# AD590.net
KiCad netlist of a schematic drawn in EAGLE
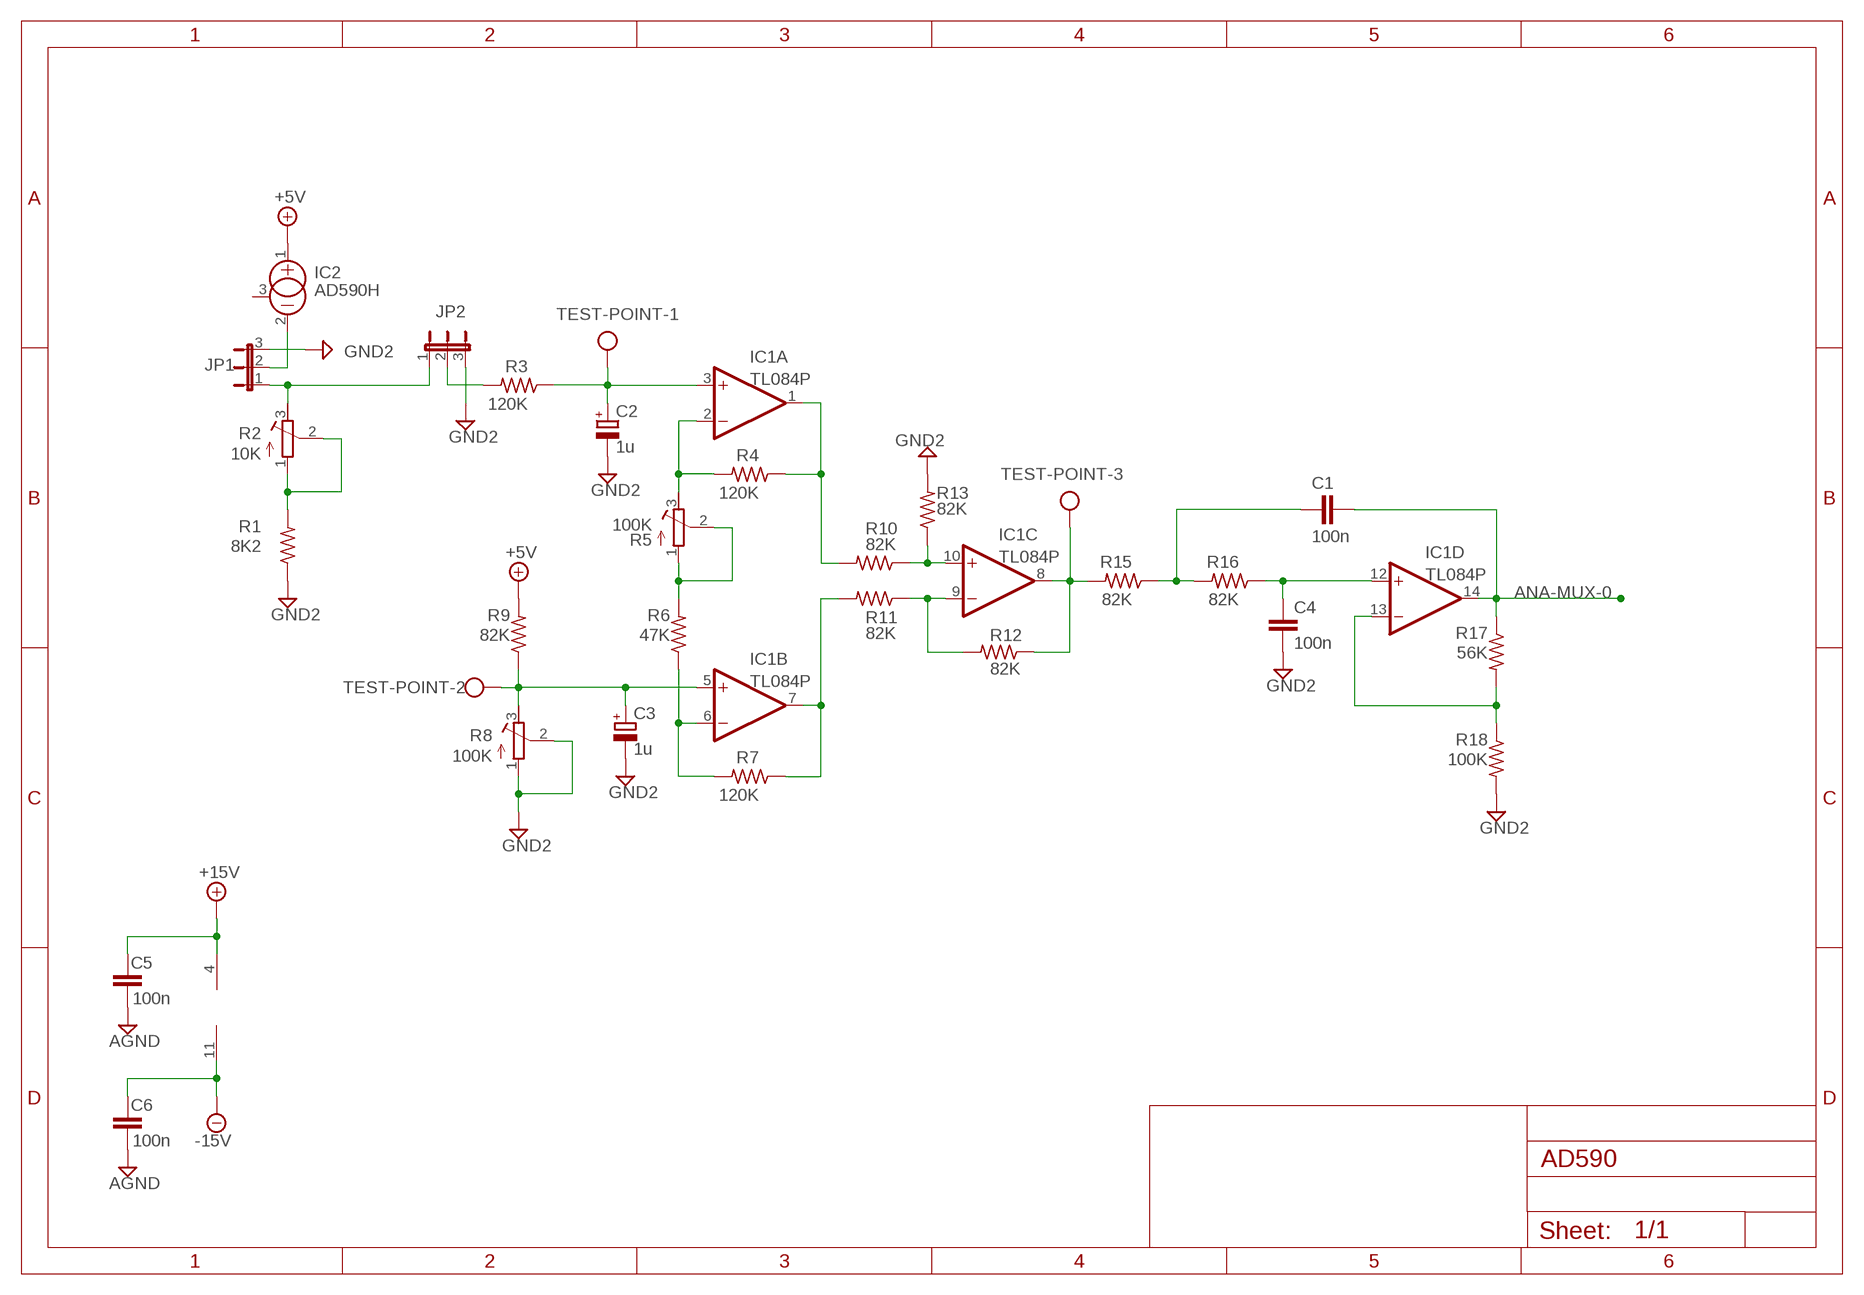
[diagram p0: schematic, sheet 1]

(export (version "E")
  (design (tool "Eeschema 10.0.6"))
  (components
    (comp (ref "C1")
      (value "100n")
      (footprint "eagle-import:C025-024X044")
      (libsource (lib "eagle-import") (part "C-EU025-024X044"))
    )
    (comp (ref "C2")
      (value "1u")
      (footprint "eagle-import:B45181C")
      (libsource (lib "eagle-import") (part "CPOL-EUB45181C"))
    )
    (comp (ref "C3")
      (value "1u")
      (footprint "eagle-import:B45181C")
      (libsource (lib "eagle-import") (part "CPOL-EUB45181C"))
    )
    (comp (ref "C4")
      (value "100n")
      (footprint "eagle-import:C025-024X044")
      (libsource (lib "eagle-import") (part "C-EU025-024X044"))
    )
    (comp (ref "C5")
      (value "100n")
      (footprint "eagle-import:C025-024X044")
      (libsource (lib "eagle-import") (part "C-EU025-024X044"))
    )
    (comp (ref "C6")
      (value "100n")
      (footprint "eagle-import:C025-024X044")
      (libsource (lib "eagle-import") (part "C-EU025-024X044"))
    )
    (comp (ref "IC1")
      (value "TL084P")
      (footprint "eagle-import:DIL14")
      (libsource (lib "eagle-import") (part "TL084P"))
    )
    (comp (ref "IC2")
      (value "AD590H")
      (footprint "eagle-import:TO18")
      (libsource (lib "eagle-import") (part "AD590H"))
    )
    (comp (ref "JP1")
      (value "JP2E")
      (footprint "eagle-import:JP2")
      (libsource (lib "eagle-import") (part "JP2E"))
    )
    (comp (ref "JP2")
      (value "JP2E")
      (footprint "eagle-import:JP2")
      (libsource (lib "eagle-import") (part "JP2E"))
    )
    (comp (ref "R1")
      (value "8K2")
      (footprint "eagle-import:0204_7")
      (libsource (lib "eagle-import") (part "R-US_0204/7"))
    )
    (comp (ref "R2")
      (value "10K")
      (footprint "eagle-import:RTRIM64W")
      (libsource (lib "eagle-import") (part "R-TRIMM64W"))
    )
    (comp (ref "R3")
      (value "120K")
      (footprint "eagle-import:0204_7")
      (libsource (lib "eagle-import") (part "R-US_0204/7"))
    )
    (comp (ref "R4")
      (value "120K")
      (footprint "eagle-import:0204_7")
      (libsource (lib "eagle-import") (part "R-US_0204/7"))
    )
    (comp (ref "R5")
      (value "100K")
      (footprint "eagle-import:RTRIM64W")
      (libsource (lib "eagle-import") (part "R-TRIMM64W"))
    )
    (comp (ref "R6")
      (value "47K")
      (footprint "eagle-import:0204_7")
      (libsource (lib "eagle-import") (part "R-US_0204/7"))
    )
    (comp (ref "R7")
      (value "120K")
      (footprint "eagle-import:0204_7")
      (libsource (lib "eagle-import") (part "R-US_0204/7"))
    )
    (comp (ref "R8")
      (value "100K")
      (footprint "eagle-import:RTRIM64W")
      (libsource (lib "eagle-import") (part "R-TRIMM64W"))
    )
    (comp (ref "R9")
      (value "82K")
      (footprint "eagle-import:0204_7")
      (libsource (lib "eagle-import") (part "R-US_0204/7"))
    )
    (comp (ref "R10")
      (value "82K")
      (footprint "eagle-import:0204_7")
      (libsource (lib "eagle-import") (part "R-US_0204/7"))
    )
    (comp (ref "R11")
      (value "82K")
      (footprint "eagle-import:0204_7")
      (libsource (lib "eagle-import") (part "R-US_0204/7"))
    )
    (comp (ref "R12")
      (value "82K")
      (footprint "eagle-import:0204_7")
      (libsource (lib "eagle-import") (part "R-US_0204/7"))
    )
    (comp (ref "R13")
      (value "82K")
      (footprint "eagle-import:0204_7")
      (libsource (lib "eagle-import") (part "R-US_0204/7"))
    )
    (comp (ref "R15")
      (value "82K")
      (footprint "eagle-import:0204_7")
      (libsource (lib "eagle-import") (part "R-US_0204/7"))
    )
    (comp (ref "R16")
      (value "82K")
      (footprint "eagle-import:0204_7")
      (libsource (lib "eagle-import") (part "R-US_0204/7"))
    )
    (comp (ref "R17")
      (value "56K")
      (footprint "eagle-import:0204_7")
      (libsource (lib "eagle-import") (part "R-US_0204/7"))
    )
    (comp (ref "R18")
      (value "100K")
      (footprint "eagle-import:0204_7")
      (libsource (lib "eagle-import") (part "R-US_0204/7"))
    )
    (comp (ref "TEST-POINT")
      (value "W237-103")
      (footprint "eagle-import:W237-103")
      (fields (field (name "MPN") "237-103"))
      (libsource (lib "eagle-import") (part "W237-103"))
    )
  )
  (nets
    (net (code "1") (name "+5V") (class "Default")
      (node (ref "IC2") (pin "1") (pinfunction "+_1") (pintype "input"))
      (node (ref "R9") (pin "2") (pinfunction "2_2") (pintype "passive"))
    )
    (net (code "2") (name "+15V") (class "Default")
      (node (ref "C5") (pin "2") (pinfunction "2_2") (pintype "passive"))
      (node (ref "IC1") (pin "4") (pinfunction "V+_4") (pintype "power_in"))
    )
    (net (code "3") (name "-15V") (class "Default")
      (node (ref "C6") (pin "2") (pinfunction "2_2") (pintype "passive"))
      (node (ref "IC1") (pin "11") (pinfunction "V-_11") (pintype "power_in"))
    )
    (net (code "4") (name "/ANA-MUX-0") (class "Default")
      (node (ref "C1") (pin "2") (pinfunction "2_2") (pintype "passive"))
      (node (ref "IC1") (pin "14") (pinfunction "OUT_14") (pintype "output"))
      (node (ref "R17") (pin "1") (pinfunction "1_1") (pintype "passive"))
    )
    (net (code "5") (name "AGND") (class "Default")
      (node (ref "C5") (pin "1") (pinfunction "1_1") (pintype "passive"))
      (node (ref "C6") (pin "1") (pinfunction "1_1") (pintype "passive"))
    )
    (net (code "6") (name "GND2") (class "Default")
      (node (ref "C2") (pin "-") (pinfunction "-_-") (pintype "passive"))
      (node (ref "C3") (pin "-") (pinfunction "-_-") (pintype "passive"))
      (node (ref "C4") (pin "1") (pinfunction "1_1") (pintype "passive"))
      (node (ref "JP1") (pin "3") (pinfunction "3_3") (pintype "passive"))
      (node (ref "JP2") (pin "3") (pinfunction "3_3") (pintype "passive"))
      (node (ref "R1") (pin "1") (pinfunction "1_1") (pintype "passive"))
      (node (ref "R13") (pin "2") (pinfunction "2_2") (pintype "passive"))
      (node (ref "R18") (pin "2") (pinfunction "2_2") (pintype "passive"))
      (node (ref "R8") (pin "1") (pinfunction "E_1") (pintype "passive"))
      (node (ref "R8") (pin "2") (pinfunction "S_2") (pintype "passive"))
    )
    (net (code "7") (name "Net-(C1-Pad1)") (class "Default")
      (node (ref "C1") (pin "1") (pinfunction "1_1") (pintype "passive"))
      (node (ref "R15") (pin "1") (pinfunction "1_1") (pintype "passive"))
      (node (ref "R16") (pin "2") (pinfunction "2_2") (pintype "passive"))
    )
    (net (code "8") (name "Net-(IC1A-+IN)") (class "Default")
      (node (ref "C2") (pin "+") (pinfunction "+_+") (pintype "passive"))
      (node (ref "IC1") (pin "3") (pinfunction "+IN_3") (pintype "input"))
      (node (ref "R3") (pin "1") (pinfunction "1_1") (pintype "passive"))
      (node (ref "TEST-POINT") (pin "1") (pinfunction "KL_1") (pintype "passive"))
    )
    (net (code "9") (name "Net-(IC1A--IN)") (class "Default")
      (node (ref "IC1") (pin "2") (pinfunction "-IN_2") (pintype "input"))
      (node (ref "R4") (pin "2") (pinfunction "2_2") (pintype "passive"))
      (node (ref "R5") (pin "3") (pinfunction "A_3") (pintype "passive"))
    )
    (net (code "10") (name "Net-(IC1A-OUT)") (class "Default")
      (node (ref "IC1") (pin "1") (pinfunction "OUT_1") (pintype "output"))
      (node (ref "R10") (pin "2") (pinfunction "2_2") (pintype "passive"))
      (node (ref "R4") (pin "1") (pinfunction "1_1") (pintype "passive"))
    )
    (net (code "11") (name "Net-(IC1B-+IN)") (class "Default")
      (node (ref "C3") (pin "+") (pinfunction "+_+") (pintype "passive"))
      (node (ref "IC1") (pin "5") (pinfunction "+IN_5") (pintype "input"))
      (node (ref "R8") (pin "3") (pinfunction "A_3") (pintype "passive"))
      (node (ref "R9") (pin "1") (pinfunction "1_1") (pintype "passive"))
      (node (ref "TEST-POINT") (pin "2") (pinfunction "KL_2") (pintype "passive"))
    )
    (net (code "12") (name "Net-(IC1B--IN)") (class "Default")
      (node (ref "IC1") (pin "6") (pinfunction "-IN_6") (pintype "input"))
      (node (ref "R6") (pin "1") (pinfunction "1_1") (pintype "passive"))
      (node (ref "R7") (pin "2") (pinfunction "2_2") (pintype "passive"))
    )
    (net (code "13") (name "Net-(IC1B-OUT)") (class "Default")
      (node (ref "IC1") (pin "7") (pinfunction "OUT_7") (pintype "output"))
      (node (ref "R11") (pin "2") (pinfunction "2_2") (pintype "passive"))
      (node (ref "R7") (pin "1") (pinfunction "1_1") (pintype "passive"))
    )
    (net (code "14") (name "Net-(IC1C-+IN)") (class "Default")
      (node (ref "IC1") (pin "10") (pinfunction "+IN_10") (pintype "input"))
      (node (ref "R10") (pin "1") (pinfunction "1_1") (pintype "passive"))
      (node (ref "R13") (pin "1") (pinfunction "1_1") (pintype "passive"))
    )
    (net (code "15") (name "Net-(IC1C--IN)") (class "Default")
      (node (ref "IC1") (pin "9") (pinfunction "-IN_9") (pintype "input"))
      (node (ref "R11") (pin "1") (pinfunction "1_1") (pintype "passive"))
      (node (ref "R12") (pin "2") (pinfunction "2_2") (pintype "passive"))
    )
    (net (code "16") (name "Net-(IC1C-OUT)") (class "Default")
      (node (ref "IC1") (pin "8") (pinfunction "OUT_8") (pintype "output"))
      (node (ref "R12") (pin "1") (pinfunction "1_1") (pintype "passive"))
      (node (ref "R15") (pin "2") (pinfunction "2_2") (pintype "passive"))
      (node (ref "TEST-POINT") (pin "3") (pinfunction "KL_3") (pintype "passive"))
    )
    (net (code "17") (name "Net-(IC1D-+IN)") (class "Default")
      (node (ref "C4") (pin "2") (pinfunction "2_2") (pintype "passive"))
      (node (ref "IC1") (pin "12") (pinfunction "+IN_12") (pintype "input"))
      (node (ref "R16") (pin "1") (pinfunction "1_1") (pintype "passive"))
    )
    (net (code "18") (name "Net-(IC1D--IN)") (class "Default")
      (node (ref "IC1") (pin "13") (pinfunction "-IN_13") (pintype "input"))
      (node (ref "R17") (pin "2") (pinfunction "2_2") (pintype "passive"))
      (node (ref "R18") (pin "1") (pinfunction "1_1") (pintype "passive"))
    )
    (net (code "19") (name "Net-(IC2--)") (class "Default")
      (node (ref "IC2") (pin "2") (pinfunction "-_2") (pintype "input"))
      (node (ref "JP1") (pin "2") (pinfunction "2_2") (pintype "passive"))
    )
    (net (code "20") (name "Net-(JP2-Pad2)") (class "Default")
      (node (ref "JP2") (pin "2") (pinfunction "2_2") (pintype "passive"))
      (node (ref "R3") (pin "2") (pinfunction "2_2") (pintype "passive"))
    )
    (net (code "21") (name "Net-(R2-A)") (class "Default")
      (node (ref "JP1") (pin "1") (pinfunction "1_1") (pintype "passive"))
      (node (ref "JP2") (pin "1") (pinfunction "1_1") (pintype "passive"))
      (node (ref "R2") (pin "3") (pinfunction "A_3") (pintype "passive"))
    )
    (net (code "22") (name "Net-(R2-E)") (class "Default")
      (node (ref "R1") (pin "2") (pinfunction "2_2") (pintype "passive"))
      (node (ref "R2") (pin "1") (pinfunction "E_1") (pintype "passive"))
      (node (ref "R2") (pin "2") (pinfunction "S_2") (pintype "passive"))
    )
    (net (code "23") (name "Net-(R5-E)") (class "Default")
      (node (ref "R5") (pin "1") (pinfunction "E_1") (pintype "passive"))
      (node (ref "R5") (pin "2") (pinfunction "S_2") (pintype "passive"))
      (node (ref "R6") (pin "2") (pinfunction "2_2") (pintype "passive"))
    )
    (net (code "24") (name "unconnected-(IC2-CAN-Pad3)") (class "Default")
      (node (ref "IC2") (pin "3") (pinfunction "CAN_3") (pintype "passive"))
    )
  )
)
